# LCD_Sheet.net
KiCad netlist of a schematic drawn in Altium Designer
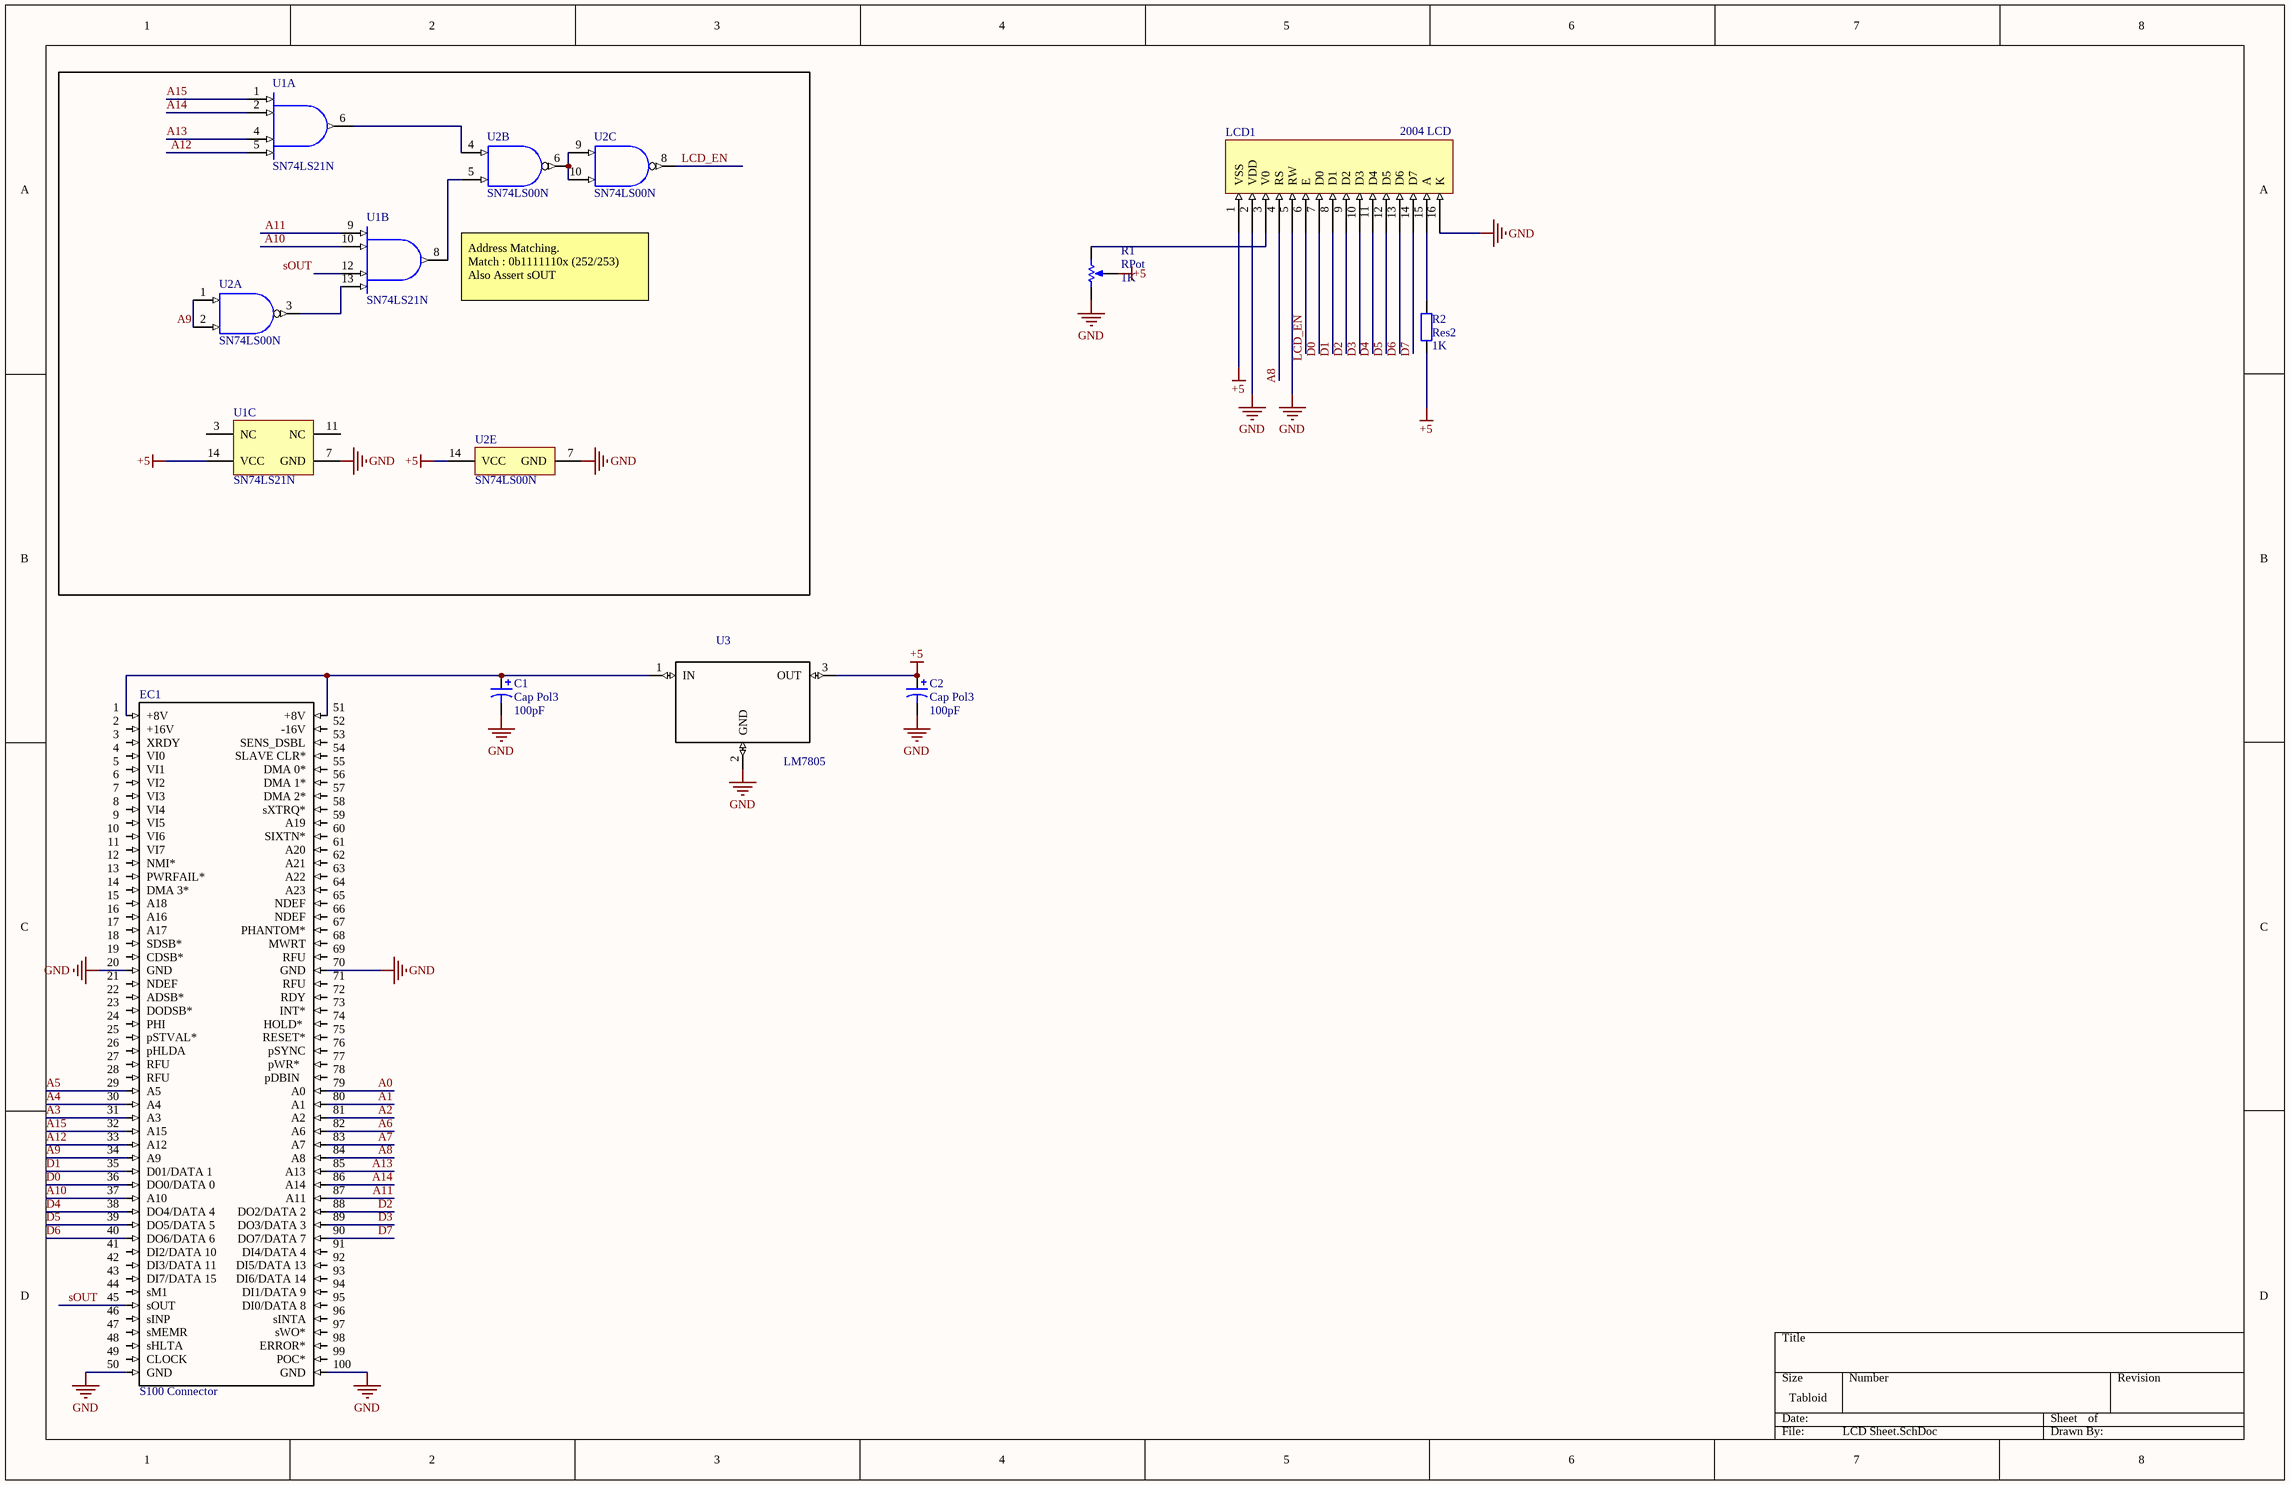
[diagram p0: LCD Sheet.SchDoc]

(export (version "E")
  (design (tool "Eeschema 10.0.6"))
  (components
    (comp (ref "C1")
      (value "Cap Pol3")
      (footprint "C0805")
      (description "Polarized Capacitor (Surface Mount)")
      (fields (field (name "ALTIUM_VALUE") "100pF") (field (name "PUBLISHER") "Altium Limited"))
      (libsource (lib "Miscellaneous Devices") (part "Cap Pol3"))
    )
    (comp (ref "C2")
      (value "Cap Pol3")
      (footprint "C0805")
      (description "Polarized Capacitor (Surface Mount)")
      (fields (field (name "ALTIUM_VALUE") "100pF") (field (name "PUBLISHER") "Altium Limited"))
      (libsource (lib "Miscellaneous Devices") (part "Cap Pol3"))
    )
    (comp (ref "EC1")
      (value "S100 Connector")
      (footprint "S100")
      (libsource (lib "S100 Breakout SCHLIB") (part "S100 Connector"))
    )
    (comp (ref "LCD1")
      (value "2004 LCD")
      (footprint "2004LCD")
      (libsource (lib "2004LCDBoardSchLib") (part "2004 LCD"))
    )
    (comp (ref "R1")
      (value "RPot")
      (footprint "VR5")
      (description "Potentiometer")
      (fields (field (name "ALTIUM_VALUE") "1K") (field (name "PUBLISHER") "Altium Limited"))
      (libsource (lib "Miscellaneous Devices") (part "RPot"))
    )
    (comp (ref "R2")
      (value "Res2")
      (footprint "AXIAL-0.4")
      (description "Resistor")
      (fields (field (name "ALTIUM_VALUE") "1K") (field (name "PUBLISHER") "Altium Limited"))
      (libsource (lib "Miscellaneous Devices") (part "Res2"))
    )
    (comp (ref "U1")
      (value "SN74LS21N")
      (footprint "N0014A")
      (description "Dual 4-input positive-AND gates, N0014A, TUBE")
      (fields
        (field (name "GENERIC PART NUMBER") "SN74LS21")
        (field (name "MANUFACTURER") "Texas Instruments")
      )
      (libsource (lib "TI_Logic_Gate") (part "SN74LS21N"))
    )
    (comp (ref "U2")
      (value "SN74LS00N")
      (footprint "N0014A")
      (description "Quad 2-input positive-NAND gates, N0014A, TUBE")
      (fields
        (field (name "GENERIC PART NUMBER") "SN74LS00")
        (field (name "MANUFACTURER") "Texas Instruments")
      )
      (libsource (lib "TI_Logic_Gate") (part "SN74LS00N"))
    )
    (comp (ref "U3")
      (value "LM7805")
      (footprint "*TO220")
      (description "Power Management, Linear Regulators, Semiconductors and Actives")
      (fields (field (name "MF") "Fairchild Semiconductor"))
      (libsource (lib "2004LCDBoardSchLib") (part "LM7805"))
    )
  )
  (nets
    (net (code "1") (name "+5") (class "Default")
      (node (ref "C2") (pin "1") (pinfunction "1_1") (pintype "passive"))
      (node (ref "LCD1") (pin "1") (pinfunction "VSS_1") (pintype "input"))
      (node (ref "R1") (pin "3") (pinfunction "TAP_3") (pintype "passive"))
      (node (ref "R2") (pin "1") (pinfunction "1_1") (pintype "passive"))
      (node (ref "U1") (pin "14") (pinfunction "VCC_14") (pintype "power_in"))
      (node (ref "U2") (pin "14") (pinfunction "VCC_14") (pintype "power_in"))
      (node (ref "U3") (pin "3") (pinfunction "OUT_3") (pintype "bidirectional"))
    )
    (net (code "2") (name "/A0") (class "Default")
      (node (ref "EC1") (pin "79") (pinfunction "A0_79") (pintype "input"))
    )
    (net (code "3") (name "/A1") (class "Default")
      (node (ref "EC1") (pin "80") (pinfunction "A1_80") (pintype "input"))
    )
    (net (code "4") (name "/A2") (class "Default")
      (node (ref "EC1") (pin "81") (pinfunction "A2_81") (pintype "input"))
    )
    (net (code "5") (name "/A3") (class "Default")
      (node (ref "EC1") (pin "31") (pinfunction "A3_31") (pintype "input"))
    )
    (net (code "6") (name "/A4") (class "Default")
      (node (ref "EC1") (pin "30") (pinfunction "A4_30") (pintype "input"))
    )
    (net (code "7") (name "/A5") (class "Default")
      (node (ref "EC1") (pin "29") (pinfunction "A5_29") (pintype "input"))
    )
    (net (code "8") (name "/A6") (class "Default")
      (node (ref "EC1") (pin "82") (pinfunction "A6_82") (pintype "input"))
    )
    (net (code "9") (name "/A7") (class "Default")
      (node (ref "EC1") (pin "83") (pinfunction "A7_83") (pintype "input"))
    )
    (net (code "10") (name "/A8") (class "Default")
      (node (ref "EC1") (pin "84") (pinfunction "A8_84") (pintype "input"))
      (node (ref "LCD1") (pin "4") (pinfunction "RS_4") (pintype "input"))
    )
    (net (code "11") (name "/A9") (class "Default")
      (node (ref "EC1") (pin "34") (pinfunction "A9_34") (pintype "input"))
      (node (ref "U2") (pin "1") (pinfunction "1A_1") (pintype "input"))
      (node (ref "U2") (pin "2") (pinfunction "1B_2") (pintype "input"))
    )
    (net (code "12") (name "/A10") (class "Default")
      (node (ref "EC1") (pin "37") (pinfunction "A10_37") (pintype "input"))
      (node (ref "U1") (pin "10") (pinfunction "2B_10") (pintype "input"))
    )
    (net (code "13") (name "/A11") (class "Default")
      (node (ref "EC1") (pin "87") (pinfunction "A11_87") (pintype "input"))
      (node (ref "U1") (pin "9") (pinfunction "2A_9") (pintype "input"))
    )
    (net (code "14") (name "/A12") (class "Default")
      (node (ref "EC1") (pin "33") (pinfunction "A12_33") (pintype "input"))
      (node (ref "U1") (pin "5") (pinfunction "1D_5") (pintype "input"))
    )
    (net (code "15") (name "/A13") (class "Default")
      (node (ref "EC1") (pin "85") (pinfunction "A13_85") (pintype "input"))
      (node (ref "U1") (pin "4") (pinfunction "1C_4") (pintype "input"))
    )
    (net (code "16") (name "/A14") (class "Default")
      (node (ref "EC1") (pin "86") (pinfunction "A14_86") (pintype "input"))
      (node (ref "U1") (pin "2") (pinfunction "1B_2") (pintype "input"))
    )
    (net (code "17") (name "/A15") (class "Default")
      (node (ref "EC1") (pin "32") (pinfunction "A15_32") (pintype "input"))
      (node (ref "U1") (pin "1") (pinfunction "1A_1") (pintype "input"))
    )
    (net (code "18") (name "/D0") (class "Default")
      (node (ref "EC1") (pin "36") (pinfunction "DO0/DATA_0_36") (pintype "input"))
      (node (ref "LCD1") (pin "7") (pinfunction "D0_7") (pintype "input"))
    )
    (net (code "19") (name "/D1") (class "Default")
      (node (ref "EC1") (pin "35") (pinfunction "D01/DATA_1_35") (pintype "input"))
      (node (ref "LCD1") (pin "8") (pinfunction "D1_8") (pintype "input"))
    )
    (net (code "20") (name "/D2") (class "Default")
      (node (ref "EC1") (pin "88") (pinfunction "DO2/DATA_2_88") (pintype "input"))
      (node (ref "LCD1") (pin "9") (pinfunction "D2_9") (pintype "input"))
    )
    (net (code "21") (name "/D3") (class "Default")
      (node (ref "EC1") (pin "89") (pinfunction "DO3/DATA_3_89") (pintype "input"))
      (node (ref "LCD1") (pin "10") (pinfunction "D3_10") (pintype "input"))
    )
    (net (code "22") (name "/D4") (class "Default")
      (node (ref "EC1") (pin "38") (pinfunction "DO4/DATA_4_38") (pintype "input"))
      (node (ref "LCD1") (pin "11") (pinfunction "D4_11") (pintype "input"))
    )
    (net (code "23") (name "/D5") (class "Default")
      (node (ref "EC1") (pin "39") (pinfunction "DO5/DATA_5_39") (pintype "input"))
      (node (ref "LCD1") (pin "12") (pinfunction "D5_12") (pintype "input"))
    )
    (net (code "24") (name "/D6") (class "Default")
      (node (ref "EC1") (pin "40") (pinfunction "DO6/DATA_6_40") (pintype "input"))
      (node (ref "LCD1") (pin "13") (pinfunction "D6_13") (pintype "input"))
    )
    (net (code "25") (name "/D7") (class "Default")
      (node (ref "EC1") (pin "90") (pinfunction "DO7/DATA_7_90") (pintype "input"))
      (node (ref "LCD1") (pin "14") (pinfunction "D7_14") (pintype "input"))
    )
    (net (code "26") (name "/LCD_EN") (class "Default")
      (node (ref "LCD1") (pin "6") (pinfunction "E_6") (pintype "input"))
      (node (ref "U2") (pin "8") (pinfunction "3Y_8") (pintype "output"))
    )
    (net (code "27") (name "/sOUT") (class "Default")
      (node (ref "EC1") (pin "45") (pinfunction "sOUT_45") (pintype "input"))
      (node (ref "U1") (pin "12") (pinfunction "2C_12") (pintype "input"))
    )
    (net (code "28") (name "GND") (class "Default")
      (node (ref "C1") (pin "2") (pinfunction "2_2") (pintype "passive"))
      (node (ref "C2") (pin "2") (pinfunction "2_2") (pintype "passive"))
      (node (ref "EC1") (pin "100") (pinfunction "GND_100") (pintype "input"))
      (node (ref "EC1") (pin "20") (pinfunction "GND_20") (pintype "input"))
      (node (ref "EC1") (pin "50") (pinfunction "GND_50") (pintype "input"))
      (node (ref "EC1") (pin "70") (pinfunction "GND_70") (pintype "input"))
      (node (ref "LCD1") (pin "16") (pinfunction "K_16") (pintype "input"))
      (node (ref "LCD1") (pin "2") (pinfunction "VDD_2") (pintype "input"))
      (node (ref "LCD1") (pin "5") (pinfunction "RW_5") (pintype "input"))
      (node (ref "R1") (pin "1") (pinfunction "TOP_1") (pintype "passive"))
      (node (ref "U1") (pin "7") (pinfunction "GND_7") (pintype "power_in"))
      (node (ref "U2") (pin "7") (pinfunction "GND_7") (pintype "power_in"))
      (node (ref "U3") (pin "2") (pinfunction "GND_2") (pintype "bidirectional"))
    )
    (net (code "29") (name "Net-(LCD1-A)") (class "Default")
      (node (ref "LCD1") (pin "15") (pinfunction "A_15") (pintype "input"))
      (node (ref "R2") (pin "2") (pinfunction "2_2") (pintype "passive"))
    )
    (net (code "30") (name "Net-(LCD1-V0)") (class "Default")
      (node (ref "LCD1") (pin "3") (pinfunction "V0_3") (pintype "input"))
      (node (ref "R1") (pin "2") (pinfunction "BOT_2") (pintype "passive"))
    )
    (net (code "31") (name "Net-(U1A-1Y)") (class "Default")
      (node (ref "U1") (pin "6") (pinfunction "1Y_6") (pintype "output"))
      (node (ref "U2") (pin "4") (pinfunction "2A_4") (pintype "input"))
    )
    (net (code "32") (name "Net-(U1B-2D)") (class "Default")
      (node (ref "U1") (pin "13") (pinfunction "2D_13") (pintype "input"))
      (node (ref "U2") (pin "3") (pinfunction "1Y_3") (pintype "output"))
    )
    (net (code "33") (name "Net-(U1B-2Y)") (class "Default")
      (node (ref "U1") (pin "8") (pinfunction "2Y_8") (pintype "output"))
      (node (ref "U2") (pin "5") (pinfunction "2B_5") (pintype "input"))
    )
    (net (code "34") (name "Net-(U2B-2Y)") (class "Default")
      (node (ref "U2") (pin "10") (pinfunction "3B_10") (pintype "input"))
      (node (ref "U2") (pin "6") (pinfunction "2Y_6") (pintype "output"))
      (node (ref "U2") (pin "9") (pinfunction "3A_9") (pintype "input"))
    )
    (net (code "35") (name "Net-(U3-IN)") (class "Default")
      (node (ref "C1") (pin "1") (pinfunction "1_1") (pintype "passive"))
      (node (ref "EC1") (pin "1") (pinfunction "+8V_1") (pintype "input"))
      (node (ref "EC1") (pin "51") (pinfunction "+8V_51") (pintype "input"))
      (node (ref "U3") (pin "1") (pinfunction "IN_1") (pintype "bidirectional"))
    )
    (net (code "36") (name "unconnected-(EC1-+16V-Pad2)") (class "Default")
      (node (ref "EC1") (pin "2") (pinfunction "+16V_2") (pintype "input"))
    )
    (net (code "37") (name "unconnected-(EC1--16V-Pad52)") (class "Default")
      (node (ref "EC1") (pin "52") (pinfunction "-16V_52") (pintype "input"))
    )
    (net (code "38") (name "unconnected-(EC1-A16  -Pad16)") (class "Default")
      (node (ref "EC1") (pin "16") (pinfunction "A16  _16") (pintype "input"))
    )
    (net (code "39") (name "unconnected-(EC1-A17-Pad17)") (class "Default")
      (node (ref "EC1") (pin "17") (pinfunction "A17_17") (pintype "input"))
    )
    (net (code "40") (name "unconnected-(EC1-A18 -Pad15)") (class "Default")
      (node (ref "EC1") (pin "15") (pinfunction "A18 _15") (pintype "input"))
    )
    (net (code "41") (name "unconnected-(EC1-A19-Pad59)") (class "Default")
      (node (ref "EC1") (pin "59") (pinfunction "A19_59") (pintype "input"))
    )
    (net (code "42") (name "unconnected-(EC1-A20-Pad61)") (class "Default")
      (node (ref "EC1") (pin "61") (pinfunction "A20_61") (pintype "input"))
    )
    (net (code "43") (name "unconnected-(EC1-A21-Pad62)") (class "Default")
      (node (ref "EC1") (pin "62") (pinfunction "A21_62") (pintype "input"))
    )
    (net (code "44") (name "unconnected-(EC1-A22-Pad63)") (class "Default")
      (node (ref "EC1") (pin "63") (pinfunction "A22_63") (pintype "input"))
    )
    (net (code "45") (name "unconnected-(EC1-A23-Pad64)") (class "Default")
      (node (ref "EC1") (pin "64") (pinfunction "A23_64") (pintype "input"))
    )
    (net (code "46") (name "unconnected-(EC1-ADSB*-Pad22)") (class "Default")
      (node (ref "EC1") (pin "22") (pinfunction "ADSB*_22") (pintype "input"))
    )
    (net (code "47") (name "unconnected-(EC1-CDSB*-Pad19)") (class "Default")
      (node (ref "EC1") (pin "19") (pinfunction "CDSB*_19") (pintype "input"))
    )
    (net (code "48") (name "unconnected-(EC1-CLOCK -Pad49)") (class "Default")
      (node (ref "EC1") (pin "49") (pinfunction "CLOCK _49") (pintype "input"))
    )
    (net (code "49") (name "unconnected-(EC1-DI0{slash}DATA_8-Pad95)") (class "Default")
      (node (ref "EC1") (pin "95") (pinfunction "DI0/DATA_8_95") (pintype "input"))
    )
    (net (code "50") (name "unconnected-(EC1-DI1{slash}DATA_9-Pad94)") (class "Default")
      (node (ref "EC1") (pin "94") (pinfunction "DI1/DATA_9_94") (pintype "input"))
    )
    (net (code "51") (name "unconnected-(EC1-DI2{slash}DATA_10-Pad41)") (class "Default")
      (node (ref "EC1") (pin "41") (pinfunction "DI2/DATA_10_41") (pintype "input"))
    )
    (net (code "52") (name "unconnected-(EC1-DI3{slash}DATA_11-Pad42)") (class "Default")
      (node (ref "EC1") (pin "42") (pinfunction "DI3/DATA_11_42") (pintype "input"))
    )
    (net (code "53") (name "unconnected-(EC1-DI4{slash}DATA_4-Pad91)") (class "Default")
      (node (ref "EC1") (pin "91") (pinfunction "DI4/DATA_4_91") (pintype "input"))
    )
    (net (code "54") (name "unconnected-(EC1-DI5{slash}DATA_13-Pad92)") (class "Default")
      (node (ref "EC1") (pin "92") (pinfunction "DI5/DATA_13_92") (pintype "input"))
    )
    (net (code "55") (name "unconnected-(EC1-DI6{slash}DATA_14-Pad93)") (class "Default")
      (node (ref "EC1") (pin "93") (pinfunction "DI6/DATA_14_93") (pintype "input"))
    )
    (net (code "56") (name "unconnected-(EC1-DI7{slash}DATA_15-Pad43)") (class "Default")
      (node (ref "EC1") (pin "43") (pinfunction "DI7/DATA_15_43") (pintype "input"))
    )
    (net (code "57") (name "unconnected-(EC1-DMA_0*-Pad55)") (class "Default")
      (node (ref "EC1") (pin "55") (pinfunction "DMA_0*_55") (pintype "input"))
    )
    (net (code "58") (name "unconnected-(EC1-DMA_1*-Pad56)") (class "Default")
      (node (ref "EC1") (pin "56") (pinfunction "DMA_1*_56") (pintype "input"))
    )
    (net (code "59") (name "unconnected-(EC1-DMA_2*-Pad57)") (class "Default")
      (node (ref "EC1") (pin "57") (pinfunction "DMA_2*_57") (pintype "input"))
    )
    (net (code "60") (name "unconnected-(EC1-DMA_3*-Pad14)") (class "Default")
      (node (ref "EC1") (pin "14") (pinfunction "DMA_3*_14") (pintype "input"))
    )
    (net (code "61") (name "unconnected-(EC1-DODSB*-Pad23)") (class "Default")
      (node (ref "EC1") (pin "23") (pinfunction "DODSB*_23") (pintype "input"))
    )
    (net (code "62") (name "unconnected-(EC1-ERROR*-Pad98)") (class "Default")
      (node (ref "EC1") (pin "98") (pinfunction "ERROR*_98") (pintype "input"))
    )
    (net (code "63") (name "unconnected-(EC1-HOLD* -Pad74)") (class "Default")
      (node (ref "EC1") (pin "74") (pinfunction "HOLD* _74") (pintype "input"))
    )
    (net (code "64") (name "unconnected-(EC1-INT*-Pad73)") (class "Default")
      (node (ref "EC1") (pin "73") (pinfunction "INT*_73") (pintype "input"))
    )
    (net (code "65") (name "unconnected-(EC1-MWRT-Pad68)") (class "Default")
      (node (ref "EC1") (pin "68") (pinfunction "MWRT_68") (pintype "input"))
    )
    (net (code "66") (name "unconnected-(EC1-NDEF-Pad21)") (class "Default")
      (node (ref "EC1") (pin "21") (pinfunction "NDEF_21") (pintype "input"))
    )
    (net (code "67") (name "unconnected-(EC1-NDEF-Pad65)") (class "Default")
      (node (ref "EC1") (pin "65") (pinfunction "NDEF_65") (pintype "input"))
    )
    (net (code "68") (name "unconnected-(EC1-NDEF-Pad66)") (class "Default")
      (node (ref "EC1") (pin "66") (pinfunction "NDEF_66") (pintype "input"))
    )
    (net (code "69") (name "unconnected-(EC1-NMI*-Pad12)") (class "Default")
      (node (ref "EC1") (pin "12") (pinfunction "NMI*_12") (pintype "input"))
    )
    (net (code "70") (name "unconnected-(EC1-PHANTOM*-Pad67)") (class "Default")
      (node (ref "EC1") (pin "67") (pinfunction "PHANTOM*_67") (pintype "input"))
    )
    (net (code "71") (name "unconnected-(EC1-PHI-Pad24)") (class "Default")
      (node (ref "EC1") (pin "24") (pinfunction "PHI_24") (pintype "input"))
    )
    (net (code "72") (name "unconnected-(EC1-POC*-Pad99)") (class "Default")
      (node (ref "EC1") (pin "99") (pinfunction "POC*_99") (pintype "input"))
    )
    (net (code "73") (name "unconnected-(EC1-PWRFAIL*-Pad13)") (class "Default")
      (node (ref "EC1") (pin "13") (pinfunction "PWRFAIL*_13") (pintype "input"))
    )
    (net (code "74") (name "unconnected-(EC1-RDY-Pad72)") (class "Default")
      (node (ref "EC1") (pin "72") (pinfunction "RDY_72") (pintype "input"))
    )
    (net (code "75") (name "unconnected-(EC1-RESET*-Pad75)") (class "Default")
      (node (ref "EC1") (pin "75") (pinfunction "RESET*_75") (pintype "input"))
    )
    (net (code "76") (name "unconnected-(EC1-RFU-Pad27)") (class "Default")
      (node (ref "EC1") (pin "27") (pinfunction "RFU_27") (pintype "input"))
    )
    (net (code "77") (name "unconnected-(EC1-RFU-Pad28)") (class "Default")
      (node (ref "EC1") (pin "28") (pinfunction "RFU_28") (pintype "input"))
    )
    (net (code "78") (name "unconnected-(EC1-RFU-Pad69)") (class "Default")
      (node (ref "EC1") (pin "69") (pinfunction "RFU_69") (pintype "input"))
    )
    (net (code "79") (name "unconnected-(EC1-RFU-Pad71)") (class "Default")
      (node (ref "EC1") (pin "71") (pinfunction "RFU_71") (pintype "input"))
    )
    (net (code "80") (name "unconnected-(EC1-SDSB*-Pad18)") (class "Default")
      (node (ref "EC1") (pin "18") (pinfunction "SDSB*_18") (pintype "input"))
    )
    (net (code "81") (name "unconnected-(EC1-SENS_DSBL-Pad53)") (class "Default")
      (node (ref "EC1") (pin "53") (pinfunction "SENS_DSBL_53") (pintype "input"))
    )
    (net (code "82") (name "unconnected-(EC1-SIXTN*-Pad60)") (class "Default")
      (node (ref "EC1") (pin "60") (pinfunction "SIXTN*_60") (pintype "input"))
    )
    (net (code "83") (name "unconnected-(EC1-SLAVE_CLR*-Pad54)") (class "Default")
      (node (ref "EC1") (pin "54") (pinfunction "SLAVE_CLR*_54") (pintype "input"))
    )
    (net (code "84") (name "unconnected-(EC1-VI0-Pad4)") (class "Default")
      (node (ref "EC1") (pin "4") (pinfunction "VI0_4") (pintype "input"))
    )
    (net (code "85") (name "unconnected-(EC1-VI1-Pad5)") (class "Default")
      (node (ref "EC1") (pin "5") (pinfunction "VI1_5") (pintype "input"))
    )
    (net (code "86") (name "unconnected-(EC1-VI2-Pad6)") (class "Default")
      (node (ref "EC1") (pin "6") (pinfunction "VI2_6") (pintype "input"))
    )
    (net (code "87") (name "unconnected-(EC1-VI3-Pad7)") (class "Default")
      (node (ref "EC1") (pin "7") (pinfunction "VI3_7") (pintype "input"))
    )
    (net (code "88") (name "unconnected-(EC1-VI4-Pad8)") (class "Default")
      (node (ref "EC1") (pin "8") (pinfunction "VI4_8") (pintype "input"))
    )
    (net (code "89") (name "unconnected-(EC1-VI5-Pad9)") (class "Default")
      (node (ref "EC1") (pin "9") (pinfunction "VI5_9") (pintype "input"))
    )
    (net (code "90") (name "unconnected-(EC1-VI6-Pad10)") (class "Default")
      (node (ref "EC1") (pin "10") (pinfunction "VI6_10") (pintype "input"))
    )
    (net (code "91") (name "unconnected-(EC1-VI7-Pad11)") (class "Default")
      (node (ref "EC1") (pin "11") (pinfunction "VI7_11") (pintype "input"))
    )
    (net (code "92") (name "unconnected-(EC1-XRDY-Pad3)") (class "Default")
      (node (ref "EC1") (pin "3") (pinfunction "XRDY_3") (pintype "input"))
    )
    (net (code "93") (name "unconnected-(EC1-pDBIN  -Pad78)") (class "Default")
      (node (ref "EC1") (pin "78") (pinfunction "pDBIN  _78") (pintype "input"))
    )
    (net (code "94") (name "unconnected-(EC1-pHLDA-Pad26)") (class "Default")
      (node (ref "EC1") (pin "26") (pinfunction "pHLDA_26") (pintype "input"))
    )
    (net (code "95") (name "unconnected-(EC1-pSTVAL*-Pad25)") (class "Default")
      (node (ref "EC1") (pin "25") (pinfunction "pSTVAL*_25") (pintype "input"))
    )
    (net (code "96") (name "unconnected-(EC1-pSYNC-Pad76)") (class "Default")
      (node (ref "EC1") (pin "76") (pinfunction "pSYNC_76") (pintype "input"))
    )
    (net (code "97") (name "unconnected-(EC1-pWR*  -Pad77)") (class "Default")
      (node (ref "EC1") (pin "77") (pinfunction "pWR*  _77") (pintype "input"))
    )
    (net (code "98") (name "unconnected-(EC1-sHLTA-Pad48)") (class "Default")
      (node (ref "EC1") (pin "48") (pinfunction "sHLTA_48") (pintype "input"))
    )
    (net (code "99") (name "unconnected-(EC1-sINP-Pad46)") (class "Default")
      (node (ref "EC1") (pin "46") (pinfunction "sINP_46") (pintype "input"))
    )
    (net (code "100") (name "unconnected-(EC1-sINTA-Pad96)") (class "Default")
      (node (ref "EC1") (pin "96") (pinfunction "sINTA_96") (pintype "input"))
    )
    (net (code "101") (name "unconnected-(EC1-sM1-Pad44)") (class "Default")
      (node (ref "EC1") (pin "44") (pinfunction "sM1_44") (pintype "input"))
    )
    (net (code "102") (name "unconnected-(EC1-sMEMR-Pad47)") (class "Default")
      (node (ref "EC1") (pin "47") (pinfunction "sMEMR_47") (pintype "input"))
    )
    (net (code "103") (name "unconnected-(EC1-sWO*-Pad97)") (class "Default")
      (node (ref "EC1") (pin "97") (pinfunction "sWO*_97") (pintype "input"))
    )
    (net (code "104") (name "unconnected-(EC1-sXTRQ*-Pad58)") (class "Default")
      (node (ref "EC1") (pin "58") (pinfunction "sXTRQ*_58") (pintype "input"))
    )
    (net (code "105") (name "unconnected-(U1C-NC-Pad3)") (class "Default")
      (node (ref "U1") (pin "3") (pinfunction "NC_3") (pintype "passive"))
    )
    (net (code "106") (name "unconnected-(U1C-NC-Pad11)") (class "Default")
      (node (ref "U1") (pin "11") (pinfunction "NC_11") (pintype "passive"))
    )
  )
)
